# Simple-Transmitter-2SC9014.net
KiCad netlist of a schematic drawn in EAGLE
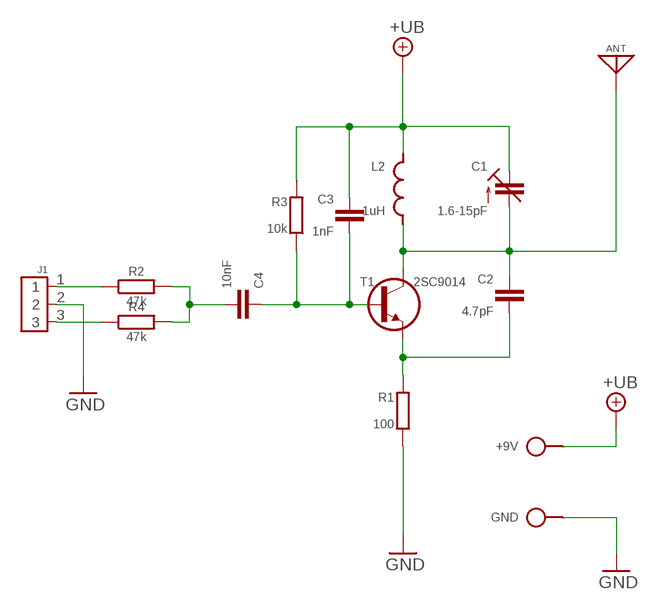
[diagram p0: schematic, sheet 1]

(export (version "E")
  (design (tool "Eeschema 10.0.6"))
  (components
    (comp (ref "+9V")
      (value "SPAD")
      (footprint "eagle-import:SPAD")
      (libsource (lib "eagle-import") (part "SPAD"))
    )
    (comp (ref "ANT")
      (value "ANT")
      (footprint "eagle-import:SPAD")
      (libsource (lib "eagle-import") (part "ANT"))
    )
    (comp (ref "C1")
      (value "1.6-15pF")
      (footprint "eagle-import:TRIM-2222-808")
      (libsource (lib "eagle-import") (part "C-TR-PH201272222-808-2PINB"))
    )
    (comp (ref "C2")
      (value "4.7pF")
      (footprint "eagle-import:C025-015X024")
      (libsource (lib "eagle-import") (part "C025-015X024"))
    )
    (comp (ref "C3")
      (value "1nF")
      (footprint "eagle-import:C025-015X024")
      (libsource (lib "eagle-import") (part "C025-015X024"))
    )
    (comp (ref "C4")
      (value "10nF")
      (footprint "eagle-import:C050-020X036_V")
      (libsource (lib "eagle-import") (part "C050-020X036/V"))
    )
    (comp (ref "GND")
      (value "SPAD")
      (footprint "eagle-import:SPAD")
      (libsource (lib "eagle-import") (part "SPAD"))
    )
    (comp (ref "J1")
      (value "CONN-3P-3P")
      (footprint "eagle-import:CONN-3P")
      (libsource (lib "eagle-import") (part "CONN-3P-3P"))
    )
    (comp (ref "L2")
      (value "1uH")
      (footprint "eagle-import:L-04_7")
      (libsource (lib "eagle-import") (part "L-SHORT04/7"))
    )
    (comp (ref "R1")
      (value "100")
      (footprint "eagle-import:0204_2V")
      (libsource (lib "eagle-import") (part "R0204/2V"))
    )
    (comp (ref "R2")
      (value "47k")
      (footprint "eagle-import:0204_10-V")
      (libsource (lib "eagle-import") (part "R-H0204/10-V"))
    )
    (comp (ref "R3")
      (value "10k")
      (footprint "eagle-import:0204_10-V")
      (libsource (lib "eagle-import") (part "R0204/10-V"))
    )
    (comp (ref "R4")
      (value "47k")
      (footprint "eagle-import:0204_10-V")
      (libsource (lib "eagle-import") (part "R-H0204/10-V"))
    )
    (comp (ref "T1")
      (value "2SC9014")
      (footprint "eagle-import:TO92-EBC")
      (libsource (lib "eagle-import") (part "2SC9014"))
    )
  )
  (nets
    (net (code "1") (name "+UB") (class "Default")
      (node (ref "+9V") (pin "1") (pinfunction "P$1_1") (pintype "bidirectional"))
      (node (ref "C1") (pin "3") (pinfunction "E_3") (pintype "passive"))
      (node (ref "C3") (pin "1") (pinfunction "1_1") (pintype "passive"))
      (node (ref "L2") (pin "2") (pinfunction "2_2") (pintype "passive"))
      (node (ref "R3") (pin "1") (pinfunction "1_1") (pintype "passive"))
    )
    (net (code "2") (name "GND") (class "Default")
      (node (ref "GND") (pin "1") (pinfunction "P$1_1") (pintype "bidirectional"))
      (node (ref "J1") (pin "2") (pinfunction "2_2") (pintype "bidirectional"))
      (node (ref "R1") (pin "1") (pinfunction "2_1") (pintype "passive"))
    )
    (net (code "3") (name "Net-(C1-A)") (class "Default")
      (node (ref "ANT") (pin "1") (pinfunction "1_1") (pintype "output"))
      (node (ref "C1") (pin "2") (pinfunction "A_2") (pintype "passive"))
      (node (ref "C2") (pin "1") (pinfunction "1_1") (pintype "passive"))
      (node (ref "L2") (pin "1") (pinfunction "1_1") (pintype "passive"))
      (node (ref "T1") (pin "C") (pinfunction "C_C") (pintype "passive"))
    )
    (net (code "4") (name "Net-(C3-Pad2)") (class "Default")
      (node (ref "C3") (pin "2") (pinfunction "2_2") (pintype "passive"))
      (node (ref "C4") (pin "1") (pinfunction "1_1") (pintype "passive"))
      (node (ref "R3") (pin "2") (pinfunction "2_2") (pintype "passive"))
      (node (ref "T1") (pin "B") (pinfunction "B_B") (pintype "passive"))
    )
    (net (code "5") (name "Net-(C4-Pad2)") (class "Default")
      (node (ref "C4") (pin "2") (pinfunction "2_2") (pintype "passive"))
      (node (ref "R2") (pin "2") (pinfunction "2_2") (pintype "passive"))
      (node (ref "R4") (pin "2") (pinfunction "2_2") (pintype "passive"))
    )
    (net (code "6") (name "Net-(J1-Pad1)") (class "Default")
      (node (ref "J1") (pin "1") (pinfunction "1_1") (pintype "bidirectional"))
      (node (ref "R2") (pin "1") (pinfunction "1_1") (pintype "passive"))
    )
    (net (code "7") (name "Net-(J1-Pad3)") (class "Default")
      (node (ref "J1") (pin "3") (pinfunction "3_3") (pintype "bidirectional"))
      (node (ref "R4") (pin "1") (pinfunction "1_1") (pintype "passive"))
    )
    (net (code "8") (name "Net-(R1-1)") (class "Default")
      (node (ref "C2") (pin "2") (pinfunction "2_2") (pintype "passive"))
      (node (ref "R1") (pin "2") (pinfunction "1_2") (pintype "passive"))
      (node (ref "T1") (pin "E") (pinfunction "E_E") (pintype "passive"))
    )
  )
)
